# ReversePolaritySchematic.net
KiCad netlist of a schematic drawn in Altium Designer
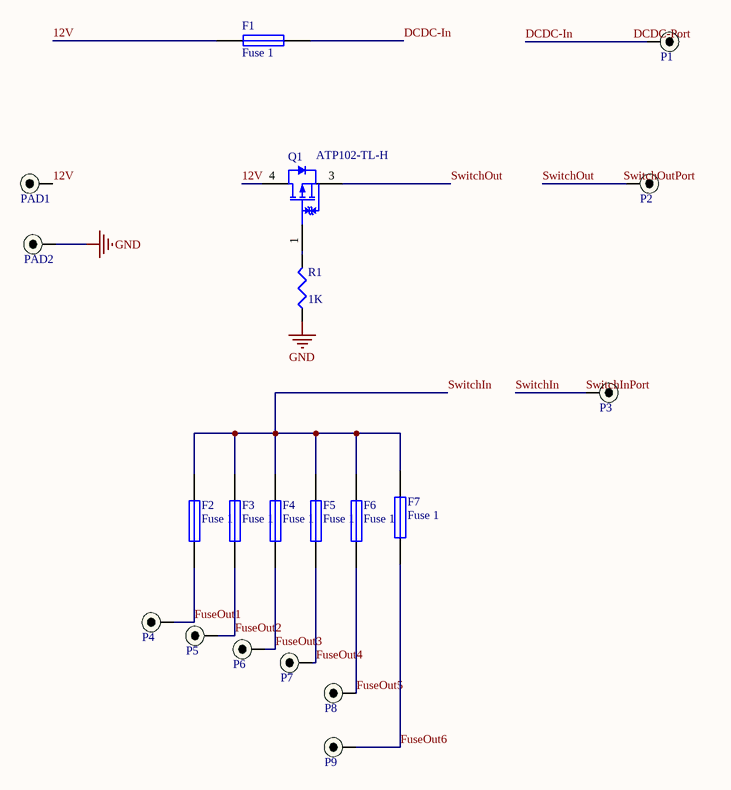
[diagram p0: ReversePolaritySchematic.SchDoc]

(export (version "E")
  (design (tool "Eeschema 10.0.6"))
  (components
    (comp (ref "F1")
      (value "Fuse 1")
      (footprint "fuseholder")
      (description "Fuse")
      (fields (field (name "PUBLISHER") "Altium Limited"))
      (libsource (lib "Miscellaneous Devices") (part "Fuse 1"))
    )
    (comp (ref "F2")
      (value "Fuse 1")
      (footprint "fuseholder")
      (description "Fuse")
      (fields (field (name "PUBLISHER") "Altium Limited"))
      (libsource (lib "Miscellaneous Devices") (part "Fuse 1"))
    )
    (comp (ref "F3")
      (value "Fuse 1")
      (footprint "fuseholder")
      (description "Fuse")
      (fields (field (name "PUBLISHER") "Altium Limited"))
      (libsource (lib "Miscellaneous Devices") (part "Fuse 1"))
    )
    (comp (ref "F4")
      (value "Fuse 1")
      (footprint "fuseholder")
      (description "Fuse")
      (fields (field (name "PUBLISHER") "Altium Limited"))
      (libsource (lib "Miscellaneous Devices") (part "Fuse 1"))
    )
    (comp (ref "F5")
      (value "Fuse 1")
      (footprint "fuseholder")
      (description "Fuse")
      (fields (field (name "PUBLISHER") "Altium Limited"))
      (libsource (lib "Miscellaneous Devices") (part "Fuse 1"))
    )
    (comp (ref "F6")
      (value "Fuse 1")
      (footprint "fuseholder")
      (description "Fuse")
      (fields (field (name "PUBLISHER") "Altium Limited"))
      (libsource (lib "Miscellaneous Devices") (part "Fuse 1"))
    )
    (comp (ref "F7")
      (value "Fuse 1")
      (footprint "fuseholder")
      (description "Fuse")
      (fields (field (name "PUBLISHER") "Altium Limited"))
      (libsource (lib "Miscellaneous Devices") (part "Fuse 1"))
    )
    (comp (ref "P1")
      (value "EXPOSED SOLDER PAD")
      (footprint "ScrewTerminalMount")
      (description "testing point")
      (libsource (lib "MFE_temp") (part "EXPOSED SOLDER PAD"))
    )
    (comp (ref "P2")
      (value "EXPOSED SOLDER PAD")
      (footprint "ScrewTerminalMount")
      (description "testing point")
      (libsource (lib "MFE_temp") (part "EXPOSED SOLDER PAD"))
    )
    (comp (ref "P3")
      (value "EXPOSED SOLDER PAD")
      (footprint "ScrewTerminalMount")
      (description "testing point")
      (libsource (lib "MFE_temp") (part "EXPOSED SOLDER PAD"))
    )
    (comp (ref "P4")
      (value "EXPOSED SOLDER PAD")
      (footprint "ScrewTerminalMount")
      (description "testing point")
      (libsource (lib "MFE_temp") (part "EXPOSED SOLDER PAD"))
    )
    (comp (ref "P5")
      (value "EXPOSED SOLDER PAD")
      (footprint "ScrewTerminalMount")
      (description "testing point")
      (libsource (lib "MFE_temp") (part "EXPOSED SOLDER PAD"))
    )
    (comp (ref "P6")
      (value "EXPOSED SOLDER PAD")
      (footprint "ScrewTerminalMount")
      (description "testing point")
      (libsource (lib "MFE_temp") (part "EXPOSED SOLDER PAD"))
    )
    (comp (ref "P7")
      (value "EXPOSED SOLDER PAD")
      (footprint "ScrewTerminalMount")
      (description "testing point")
      (libsource (lib "MFE_temp") (part "EXPOSED SOLDER PAD"))
    )
    (comp (ref "P8")
      (value "EXPOSED SOLDER PAD")
      (footprint "ScrewTerminalMount")
      (description "testing point")
      (libsource (lib "MFE_temp") (part "EXPOSED SOLDER PAD"))
    )
    (comp (ref "P9")
      (value "EXPOSED SOLDER PAD")
      (footprint "ScrewTerminalMount")
      (description "testing point")
      (libsource (lib "MFE_temp") (part "EXPOSED SOLDER PAD"))
    )
    (comp (ref "PAD1")
      (value "EXPOSED SOLDER PAD")
      (footprint "PAD - duplicate")
      (description "testing point")
      (libsource (lib "MFE_temp") (part "EXPOSED SOLDER PAD"))
    )
    (comp (ref "PAD2")
      (value "EXPOSED SOLDER PAD")
      (footprint "PAD - duplicate")
      (description "testing point")
      (libsource (lib "MFE_temp") (part "EXPOSED SOLDER PAD"))
    )
    (comp (ref "Q1")
      (value "ATP102-TL-H")
      (footprint "ONSC-ATPAK-3-369AM_V")
      (description "P-Channel Power MOSFET, -30 V, -40 A, 18.5 mOhm, Single, 3-Pin ATPAK, Pb-Free, Tape and Reel")
      (fields (field (name "MANUFACTURER") "On Semiconductor"))
      (libsource (lib "On_Semiconductor_ATP102_TL_H") (part "ATP102-TL-H"))
    )
    (comp (ref "R1")
      (value "1K")
      (footprint "14-1210")
      (description "Resistor")
      (fields (field (name "Comment") "Res3") (field (name "PUBLISHER") "Altium Limited"))
      (libsource (lib "Miscellaneous Devices") (part "Res3"))
    )
  )
  (nets
    (net (code "1") (name "/12V") (class "Default")
      (node (ref "F1") (pin "1") (pinfunction "1_1") (pintype "passive"))
      (node (ref "PAD1") (pin "1") (pinfunction "PAD_1") (pintype "passive"))
      (node (ref "Q1") (pin "4") (pinfunction "D_4") (pintype "passive"))
    )
    (net (code "2") (name "/DCDC-In") (class "Default")
      (node (ref "F1") (pin "2") (pinfunction "2_2") (pintype "passive"))
      (node (ref "P1") (pin "1") (pinfunction "PAD_1") (pintype "passive"))
    )
    (net (code "3") (name "/FuseOut1") (class "Default")
      (node (ref "F2") (pin "1") (pinfunction "1_1") (pintype "passive"))
      (node (ref "P4") (pin "1") (pinfunction "PAD_1") (pintype "passive"))
    )
    (net (code "4") (name "/FuseOut2") (class "Default")
      (node (ref "F3") (pin "1") (pinfunction "1_1") (pintype "passive"))
      (node (ref "P5") (pin "1") (pinfunction "PAD_1") (pintype "passive"))
    )
    (net (code "5") (name "/FuseOut3") (class "Default")
      (node (ref "F4") (pin "1") (pinfunction "1_1") (pintype "passive"))
      (node (ref "P6") (pin "1") (pinfunction "PAD_1") (pintype "passive"))
    )
    (net (code "6") (name "/FuseOut4") (class "Default")
      (node (ref "F5") (pin "1") (pinfunction "1_1") (pintype "passive"))
      (node (ref "P7") (pin "1") (pinfunction "PAD_1") (pintype "passive"))
    )
    (net (code "7") (name "/FuseOut5") (class "Default")
      (node (ref "F6") (pin "1") (pinfunction "1_1") (pintype "passive"))
      (node (ref "P8") (pin "1") (pinfunction "PAD_1") (pintype "passive"))
    )
    (net (code "8") (name "/FuseOut6") (class "Default")
      (node (ref "F7") (pin "1") (pinfunction "1_1") (pintype "passive"))
      (node (ref "P9") (pin "1") (pinfunction "PAD_1") (pintype "passive"))
    )
    (net (code "9") (name "/SwitchIn") (class "Default")
      (node (ref "F2") (pin "2") (pinfunction "2_2") (pintype "passive"))
      (node (ref "F3") (pin "2") (pinfunction "2_2") (pintype "passive"))
      (node (ref "F4") (pin "2") (pinfunction "2_2") (pintype "passive"))
      (node (ref "F5") (pin "2") (pinfunction "2_2") (pintype "passive"))
      (node (ref "F6") (pin "2") (pinfunction "2_2") (pintype "passive"))
      (node (ref "F7") (pin "2") (pinfunction "2_2") (pintype "passive"))
      (node (ref "P3") (pin "1") (pinfunction "PAD_1") (pintype "passive"))
    )
    (net (code "10") (name "/SwitchOut") (class "Default")
      (node (ref "P2") (pin "1") (pinfunction "PAD_1") (pintype "passive"))
      (node (ref "Q1") (pin "3") (pinfunction "S_3") (pintype "passive"))
    )
    (net (code "11") (name "GND") (class "Default")
      (node (ref "PAD2") (pin "1") (pinfunction "PAD_1") (pintype "passive"))
      (node (ref "R1") (pin "1") (pinfunction "1_1") (pintype "passive"))
    )
    (net (code "12") (name "Net-(Q1-G)") (class "Default")
      (node (ref "Q1") (pin "1") (pinfunction "G_1") (pintype "passive"))
      (node (ref "R1") (pin "2") (pinfunction "2_2") (pintype "passive"))
    )
  )
)
